# Amp_op3.net
KiCad netlist of a schematic drawn in Altium Designer
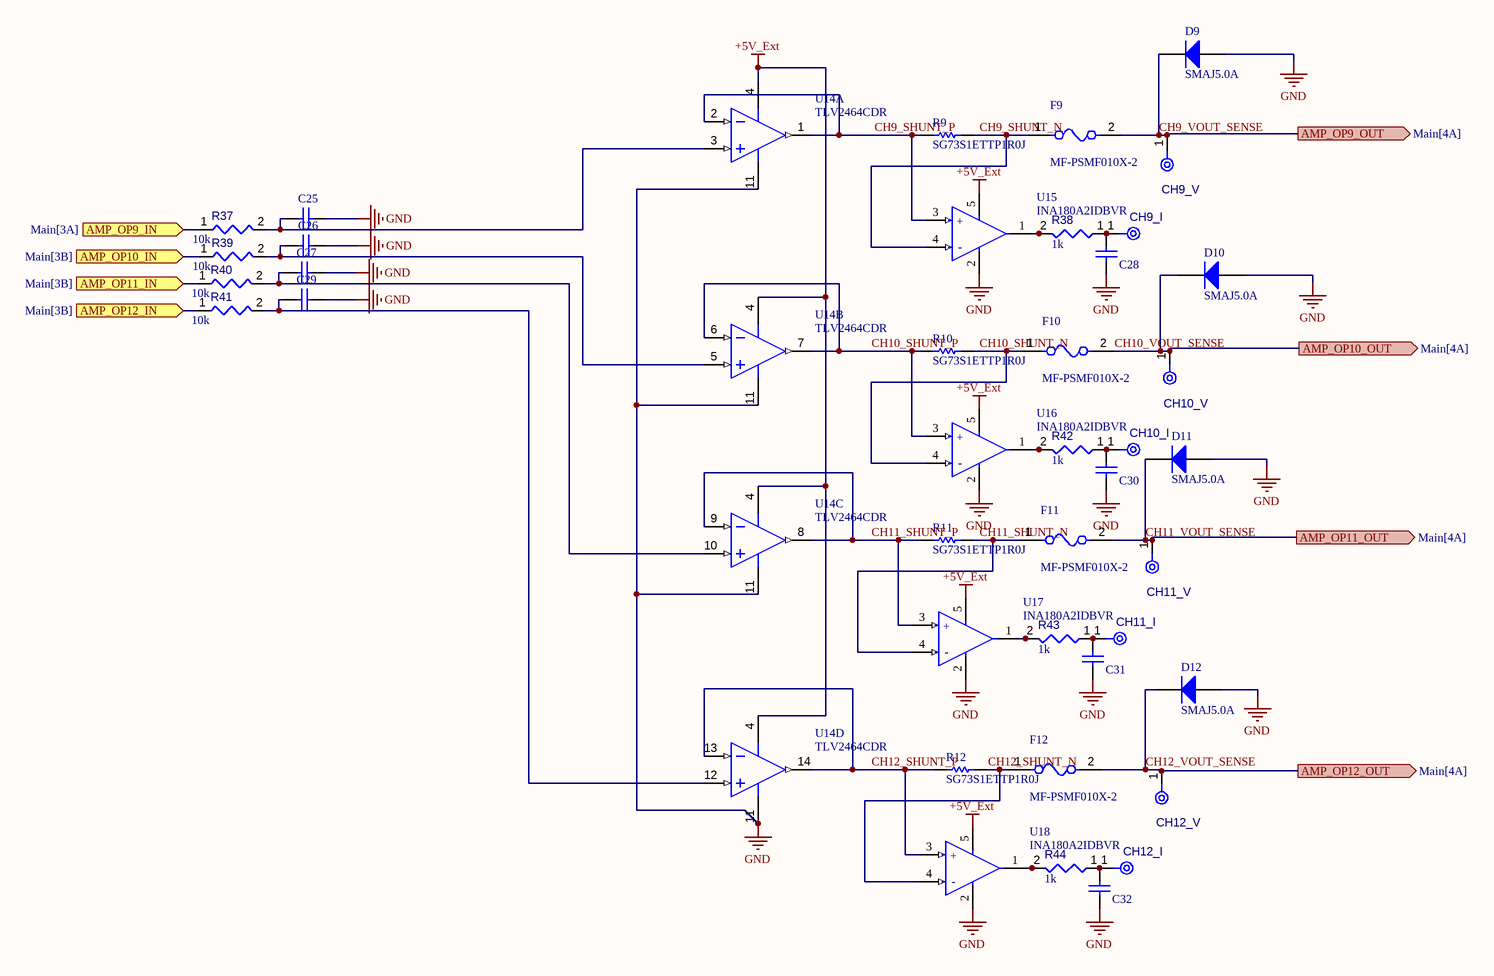
[diagram p0: Amp_op3.SchDoc]

(export (version "E")
  (design (tool "Eeschema 10.0.6"))
  (components
    (comp (ref "C25")
      (value "VJ0603Y104MXJCW1BC")
      (footprint "CAPC1608X95X40NL15T15")
      (fields (field (name "MANUFACTURER") "Vitramon"))
      (libsource (lib "Altium Content Vault") (part "CAP"))
    )
    (comp (ref "C26")
      (value "VJ0603Y104MXJCW1BC")
      (footprint "CAPC1608X95X40NL15T15")
      (fields (field (name "MANUFACTURER") "Vitramon"))
      (libsource (lib "Altium Content Vault") (part "CAP"))
    )
    (comp (ref "C27")
      (value "VJ0603Y104MXJCW1BC")
      (footprint "CAPC1608X95X40NL15T15")
      (fields (field (name "MANUFACTURER") "Vitramon"))
      (libsource (lib "Altium Content Vault") (part "CAP"))
    )
    (comp (ref "C28")
      (value "VJ0603Y104MXJCW1BC")
      (footprint "CAPC1608X95X40NL15T15")
      (fields (field (name "MANUFACTURER") "Vitramon"))
      (libsource (lib "Altium Content Vault") (part "CAP"))
    )
    (comp (ref "C29")
      (value "VJ0603Y104MXJCW1BC")
      (footprint "CAPC1608X95X40NL15T15")
      (fields (field (name "MANUFACTURER") "Vitramon"))
      (libsource (lib "Altium Content Vault") (part "CAP"))
    )
    (comp (ref "C30")
      (value "VJ0603Y104MXJCW1BC")
      (footprint "CAPC1608X95X40NL15T15")
      (fields (field (name "MANUFACTURER") "Vitramon"))
      (libsource (lib "Altium Content Vault") (part "CAP"))
    )
    (comp (ref "C31")
      (value "VJ0603Y104MXJCW1BC")
      (footprint "CAPC1608X95X40NL15T15")
      (fields (field (name "MANUFACTURER") "Vitramon"))
      (libsource (lib "Altium Content Vault") (part "CAP"))
    )
    (comp (ref "C32")
      (value "VJ0603Y104MXJCW1BC")
      (footprint "CAPC1608X95X40NL15T15")
      (fields (field (name "MANUFACTURER") "Vitramon"))
      (libsource (lib "Altium Content Vault") (part "CAP"))
    )
    (comp (ref "CH9_I")
      (value "TPAD6R")
      (footprint "TP06R")
      (description "0.6mm round")
      (libsource (lib "PCEIOT") (part "CMP-00028-00002-2"))
    )
    (comp (ref "CH9_V")
      (value "TPAD6R")
      (footprint "TP06R")
      (description "0.6mm round")
      (libsource (lib "PCEIOT") (part "CMP-00028-00002-2"))
    )
    (comp (ref "CH10_I")
      (value "TPAD6R")
      (footprint "TP06R")
      (description "0.6mm round")
      (libsource (lib "PCEIOT") (part "CMP-00028-00002-2"))
    )
    (comp (ref "CH10_V")
      (value "TPAD6R")
      (footprint "TP06R")
      (description "0.6mm round")
      (libsource (lib "PCEIOT") (part "CMP-00028-00002-2"))
    )
    (comp (ref "CH11_I")
      (value "TPAD6R")
      (footprint "TP06R")
      (description "0.6mm round")
      (libsource (lib "PCEIOT") (part "CMP-00028-00002-2"))
    )
    (comp (ref "CH11_V")
      (value "TPAD6R")
      (footprint "TP06R")
      (description "0.6mm round")
      (libsource (lib "PCEIOT") (part "CMP-00028-00002-2"))
    )
    (comp (ref "CH12_I")
      (value "TPAD6R")
      (footprint "TP06R")
      (description "0.6mm round")
      (libsource (lib "PCEIOT") (part "CMP-00028-00002-2"))
    )
    (comp (ref "CH12_V")
      (value "TPAD6R")
      (footprint "TP06R")
      (description "0.6mm round")
      (libsource (lib "PCEIOT") (part "CMP-00028-00002-2"))
    )
    (comp (ref "D9")
      (value "SMAJ5.0A")
      (footprint "BOUR-SMA-2_V")
      (fields (field (name "MANUFACTURER") "Bourns"))
      (libsource (lib "Altium Content Vault") (part "D-AK-2"))
    )
    (comp (ref "D10")
      (value "SMAJ5.0A")
      (footprint "BOUR-SMA-2_V")
      (fields (field (name "MANUFACTURER") "Bourns"))
      (libsource (lib "Altium Content Vault") (part "D-AK-2"))
    )
    (comp (ref "D11")
      (value "SMAJ5.0A")
      (footprint "BOUR-SMA-2_V")
      (fields (field (name "MANUFACTURER") "Bourns"))
      (libsource (lib "Altium Content Vault") (part "D-AK-2"))
    )
    (comp (ref "D12")
      (value "SMAJ5.0A")
      (footprint "BOUR-SMA-2_V")
      (fields (field (name "MANUFACTURER") "Bourns"))
      (libsource (lib "Altium Content Vault") (part "D-AK-2"))
    )
    (comp (ref "F9")
      (value "MF-PSMF010X-2")
      (footprint "FP-MF-PSMF-MFG")
      (description "PTC RESET FUSE 15V 100MA 0805")
      (fields
        (field (name "OCTOPART") "https://octopart.com/mf-psmf010x-2-bourns-7483441")
        (field (name "MANUFACTURER") "Bourns Inc.")
      )
      (libsource (lib "Altium Content Vault") (part "5bcf9b9f640e542cf0359d10258e979"))
    )
    (comp (ref "F10")
      (value "MF-PSMF010X-2")
      (footprint "FP-MF-PSMF-MFG")
      (description "PTC RESET FUSE 15V 100MA 0805")
      (fields
        (field (name "OCTOPART") "https://octopart.com/mf-psmf010x-2-bourns-7483441")
        (field (name "MANUFACTURER") "Bourns Inc.")
      )
      (libsource (lib "Altium Content Vault") (part "5bcf9b9f640e542cf0359d10258e979"))
    )
    (comp (ref "F11")
      (value "MF-PSMF010X-2")
      (footprint "FP-MF-PSMF-MFG")
      (description "PTC RESET FUSE 15V 100MA 0805")
      (fields
        (field (name "OCTOPART") "https://octopart.com/mf-psmf010x-2-bourns-7483441")
        (field (name "MANUFACTURER") "Bourns Inc.")
      )
      (libsource (lib "Altium Content Vault") (part "5bcf9b9f640e542cf0359d10258e979"))
    )
    (comp (ref "F12")
      (value "MF-PSMF010X-2")
      (footprint "FP-MF-PSMF-MFG")
      (description "PTC RESET FUSE 15V 100MA 0805")
      (fields
        (field (name "OCTOPART") "https://octopart.com/mf-psmf010x-2-bourns-7483441")
        (field (name "MANUFACTURER") "Bourns Inc.")
      )
      (libsource (lib "Altium Content Vault") (part "5bcf9b9f640e542cf0359d10258e979"))
    )
    (comp (ref "R9")
      (value "SG73S1ETTP1R0J")
      (footprint "RESC1005X40X25LL10T10")
      (fields (field (name "MANUFACTURER") "KOA Speer"))
      (libsource (lib "Altium Content Vault") (part "RES"))
    )
    (comp (ref "R10")
      (value "SG73S1ETTP1R0J")
      (footprint "RESC1005X40X25LL10T10")
      (fields (field (name "MANUFACTURER") "KOA Speer"))
      (libsource (lib "Altium Content Vault") (part "RES"))
    )
    (comp (ref "R11")
      (value "SG73S1ETTP1R0J")
      (footprint "RESC1005X40X25LL10T10")
      (fields (field (name "MANUFACTURER") "KOA Speer"))
      (libsource (lib "Altium Content Vault") (part "RES"))
    )
    (comp (ref "R12")
      (value "SG73S1ETTP1R0J")
      (footprint "RESC1005X40X25LL10T10")
      (fields (field (name "MANUFACTURER") "KOA Speer"))
      (libsource (lib "Altium Content Vault") (part "RES"))
    )
    (comp (ref "R37")
      (value "10k")
      (footprint "RESC0603(1608)_L")
      (description "Chip Resistor, 10 KOhm, +/- 1%, 01 W, -55 to 155 degC, 0603 (1608 Metric)")
      (fields (field (name "POWER") "100mW") (field (name "TOLERANCE") "1%"))
      (libsource (lib "PCEIOT") (part "CMP-009-00017-7"))
    )
    (comp (ref "R38")
      (value "1k")
      (footprint "RESC0603(1608)_L")
      (description "Chip Resistor, 1 KOhm, +/-1%, 0.1 W, -55 to 155 degC, 0603 (1608 Metric)")
      (fields (field (name "POWER") "100mW") (field (name "TOLERANCE") "1%"))
      (libsource (lib "PCEIOT") (part "CMP-009-00014-6"))
    )
    (comp (ref "R39")
      (value "10k")
      (footprint "RESC0603(1608)_L")
      (description "Chip Resistor, 10 KOhm, +/- 1%, 01 W, -55 to 155 degC, 0603 (1608 Metric)")
      (fields (field (name "POWER") "100mW") (field (name "TOLERANCE") "1%"))
      (libsource (lib "PCEIOT") (part "CMP-009-00017-7"))
    )
    (comp (ref "R40")
      (value "10k")
      (footprint "RESC0603(1608)_L")
      (description "Chip Resistor, 10 KOhm, +/- 1%, 01 W, -55 to 155 degC, 0603 (1608 Metric)")
      (fields (field (name "POWER") "100mW") (field (name "TOLERANCE") "1%"))
      (libsource (lib "PCEIOT") (part "CMP-009-00017-7"))
    )
    (comp (ref "R41")
      (value "10k")
      (footprint "RESC0603(1608)_L")
      (description "Chip Resistor, 10 KOhm, +/- 1%, 01 W, -55 to 155 degC, 0603 (1608 Metric)")
      (fields (field (name "POWER") "100mW") (field (name "TOLERANCE") "1%"))
      (libsource (lib "PCEIOT") (part "CMP-009-00017-7"))
    )
    (comp (ref "R42")
      (value "1k")
      (footprint "RESC0603(1608)_L")
      (description "Chip Resistor, 1 KOhm, +/-1%, 0.1 W, -55 to 155 degC, 0603 (1608 Metric)")
      (fields (field (name "POWER") "100mW") (field (name "TOLERANCE") "1%"))
      (libsource (lib "PCEIOT") (part "CMP-009-00014-6"))
    )
    (comp (ref "R43")
      (value "1k")
      (footprint "RESC0603(1608)_L")
      (description "Chip Resistor, 1 KOhm, +/-1%, 0.1 W, -55 to 155 degC, 0603 (1608 Metric)")
      (fields (field (name "POWER") "100mW") (field (name "TOLERANCE") "1%"))
      (libsource (lib "PCEIOT") (part "CMP-009-00014-6"))
    )
    (comp (ref "R44")
      (value "1k")
      (footprint "RESC0603(1608)_L")
      (description "Chip Resistor, 1 KOhm, +/-1%, 0.1 W, -55 to 155 degC, 0603 (1608 Metric)")
      (fields (field (name "POWER") "100mW") (field (name "TOLERANCE") "1%"))
      (libsource (lib "PCEIOT") (part "CMP-009-00014-6"))
    )
    (comp (ref "U14")
      (value "TLV2464CDR")
      (footprint "D0014A_N")
      (fields (field (name "MANUFACTURER") "Texas Instruments"))
      (libsource (lib "Altium Content Vault") (part "TI-TLV2464X-XX14"))
    )
    (comp (ref "U15")
      (value "INA180A2IDBVR")
      (footprint "FP-DBV0005A-MFG")
      (description "IC CURR SENSE 1 CIRCUIT SOT23-5")
      (libsource (lib "Altium Content Vault") (part "0a55cf1a948ad01a3239aec1b7efad0"))
    )
    (comp (ref "U16")
      (value "INA180A2IDBVR")
      (footprint "FP-DBV0005A-MFG")
      (description "IC CURR SENSE 1 CIRCUIT SOT23-5")
      (libsource (lib "Altium Content Vault") (part "0a55cf1a948ad01a3239aec1b7efad0"))
    )
    (comp (ref "U17")
      (value "INA180A2IDBVR")
      (footprint "FP-DBV0005A-MFG")
      (description "IC CURR SENSE 1 CIRCUIT SOT23-5")
      (libsource (lib "Altium Content Vault") (part "0a55cf1a948ad01a3239aec1b7efad0"))
    )
    (comp (ref "U18")
      (value "INA180A2IDBVR")
      (footprint "FP-DBV0005A-MFG")
      (description "IC CURR SENSE 1 CIRCUIT SOT23-5")
      (libsource (lib "Altium Content Vault") (part "0a55cf1a948ad01a3239aec1b7efad0"))
    )
  )
  (nets
    (net (code "1") (name "+5V_Ext") (class "Default")
      (node (ref "U14") (pin "4") (pinfunction "VDD+_4") (pintype "power_in"))
      (node (ref "U15") (pin "5") (pinfunction "VS_5") (pintype "power_in"))
      (node (ref "U16") (pin "5") (pinfunction "VS_5") (pintype "power_in"))
      (node (ref "U17") (pin "5") (pinfunction "VS_5") (pintype "power_in"))
      (node (ref "U18") (pin "5") (pinfunction "VS_5") (pintype "power_in"))
    )
    (net (code "2") (name "/AMP_OP9_IN") (class "Default")
      (node (ref "R37") (pin "1") (pinfunction "1_1") (pintype "passive"))
    )
    (net (code "3") (name "/AMP_OP10_IN") (class "Default")
      (node (ref "R39") (pin "1") (pinfunction "1_1") (pintype "passive"))
    )
    (net (code "4") (name "/AMP_OP11_IN") (class "Default")
      (node (ref "R40") (pin "1") (pinfunction "1_1") (pintype "passive"))
    )
    (net (code "5") (name "/AMP_OP12_IN") (class "Default")
      (node (ref "R41") (pin "1") (pinfunction "1_1") (pintype "passive"))
    )
    (net (code "6") (name "/CH9_SHUNT_N") (class "Default")
      (node (ref "F9") (pin "1") (pinfunction "1_1") (pintype "passive"))
      (node (ref "R9") (pin "2") (pinfunction "2_2") (pintype "passive"))
      (node (ref "U15") (pin "4") (pinfunction "IN-_4") (pintype "input"))
    )
    (net (code "7") (name "/CH9_SHUNT_P") (class "Default")
      (node (ref "R9") (pin "1") (pinfunction "1_1") (pintype "passive"))
      (node (ref "U14") (pin "1") (pinfunction "OUT1_1") (pintype "output"))
      (node (ref "U14") (pin "2") (pinfunction "IN1-_2") (pintype "input"))
      (node (ref "U15") (pin "3") (pinfunction "IN+_3") (pintype "input"))
    )
    (net (code "8") (name "/CH9_VOUT_SENSE") (class "Default")
      (node (ref "CH9_V") (pin "1") (pinfunction "TP_1") (pintype "passive"))
      (node (ref "D9") (pin "2") (pinfunction "K_2") (pintype "passive"))
      (node (ref "F9") (pin "2") (pinfunction "2_2") (pintype "passive"))
    )
    (net (code "9") (name "/CH10_SHUNT_N") (class "Default")
      (node (ref "F10") (pin "1") (pinfunction "1_1") (pintype "passive"))
      (node (ref "R10") (pin "2") (pinfunction "2_2") (pintype "passive"))
      (node (ref "U16") (pin "4") (pinfunction "IN-_4") (pintype "input"))
    )
    (net (code "10") (name "/CH10_SHUNT_P") (class "Default")
      (node (ref "R10") (pin "1") (pinfunction "1_1") (pintype "passive"))
      (node (ref "U14") (pin "6") (pinfunction "IN2-_6") (pintype "input"))
      (node (ref "U14") (pin "7") (pinfunction "OUT2_7") (pintype "output"))
      (node (ref "U16") (pin "3") (pinfunction "IN+_3") (pintype "input"))
    )
    (net (code "11") (name "/CH10_VOUT_SENSE") (class "Default")
      (node (ref "CH10_V") (pin "1") (pinfunction "TP_1") (pintype "passive"))
      (node (ref "D10") (pin "2") (pinfunction "K_2") (pintype "passive"))
      (node (ref "F10") (pin "2") (pinfunction "2_2") (pintype "passive"))
    )
    (net (code "12") (name "/CH11_SHUNT_N") (class "Default")
      (node (ref "F11") (pin "1") (pinfunction "1_1") (pintype "passive"))
      (node (ref "R11") (pin "2") (pinfunction "2_2") (pintype "passive"))
      (node (ref "U17") (pin "4") (pinfunction "IN-_4") (pintype "input"))
    )
    (net (code "13") (name "/CH11_SHUNT_P") (class "Default")
      (node (ref "R11") (pin "1") (pinfunction "1_1") (pintype "passive"))
      (node (ref "U14") (pin "8") (pinfunction "OUT3_8") (pintype "output"))
      (node (ref "U14") (pin "9") (pinfunction "IN3-_9") (pintype "input"))
      (node (ref "U17") (pin "3") (pinfunction "IN+_3") (pintype "input"))
    )
    (net (code "14") (name "/CH11_VOUT_SENSE") (class "Default")
      (node (ref "CH11_V") (pin "1") (pinfunction "TP_1") (pintype "passive"))
      (node (ref "D11") (pin "2") (pinfunction "K_2") (pintype "passive"))
      (node (ref "F11") (pin "2") (pinfunction "2_2") (pintype "passive"))
    )
    (net (code "15") (name "/CH12_SHUNT_N") (class "Default")
      (node (ref "F12") (pin "1") (pinfunction "1_1") (pintype "passive"))
      (node (ref "R12") (pin "2") (pinfunction "2_2") (pintype "passive"))
      (node (ref "U18") (pin "4") (pinfunction "IN-_4") (pintype "input"))
    )
    (net (code "16") (name "/CH12_SHUNT_P") (class "Default")
      (node (ref "R12") (pin "1") (pinfunction "1_1") (pintype "passive"))
      (node (ref "U14") (pin "13") (pinfunction "IN4-_13") (pintype "input"))
      (node (ref "U14") (pin "14") (pinfunction "OUT4_14") (pintype "output"))
      (node (ref "U18") (pin "3") (pinfunction "IN+_3") (pintype "input"))
    )
    (net (code "17") (name "/CH12_VOUT_SENSE") (class "Default")
      (node (ref "CH12_V") (pin "1") (pinfunction "TP_1") (pintype "passive"))
      (node (ref "D12") (pin "2") (pinfunction "K_2") (pintype "passive"))
      (node (ref "F12") (pin "2") (pinfunction "2_2") (pintype "passive"))
    )
    (net (code "18") (name "GND") (class "Default")
      (node (ref "C25") (pin "2") (pinfunction "2_2") (pintype "passive"))
      (node (ref "C26") (pin "2") (pinfunction "2_2") (pintype "passive"))
      (node (ref "C27") (pin "2") (pinfunction "2_2") (pintype "passive"))
      (node (ref "C28") (pin "2") (pinfunction "2_2") (pintype "passive"))
      (node (ref "C29") (pin "2") (pinfunction "2_2") (pintype "passive"))
      (node (ref "C30") (pin "2") (pinfunction "2_2") (pintype "passive"))
      (node (ref "C31") (pin "2") (pinfunction "2_2") (pintype "passive"))
      (node (ref "C32") (pin "2") (pinfunction "2_2") (pintype "passive"))
      (node (ref "D10") (pin "1") (pinfunction "A_1") (pintype "passive"))
      (node (ref "D11") (pin "1") (pinfunction "A_1") (pintype "passive"))
      (node (ref "D12") (pin "1") (pinfunction "A_1") (pintype "passive"))
      (node (ref "D9") (pin "1") (pinfunction "A_1") (pintype "passive"))
      (node (ref "U14") (pin "11") (pinfunction "GND_11") (pintype "power_in"))
      (node (ref "U15") (pin "2") (pinfunction "GND_2") (pintype "power_in"))
      (node (ref "U16") (pin "2") (pinfunction "GND_2") (pintype "power_in"))
      (node (ref "U17") (pin "2") (pinfunction "GND_2") (pintype "power_in"))
      (node (ref "U18") (pin "2") (pinfunction "GND_2") (pintype "power_in"))
    )
    (net (code "19") (name "Net-(CH9_I-TP)") (class "Default")
      (node (ref "C28") (pin "1") (pinfunction "1_1") (pintype "passive"))
      (node (ref "CH9_I") (pin "1") (pinfunction "TP_1") (pintype "passive"))
      (node (ref "R38") (pin "1") (pinfunction "1_1") (pintype "passive"))
    )
    (net (code "20") (name "Net-(CH10_I-TP)") (class "Default")
      (node (ref "C30") (pin "1") (pinfunction "1_1") (pintype "passive"))
      (node (ref "CH10_I") (pin "1") (pinfunction "TP_1") (pintype "passive"))
      (node (ref "R42") (pin "1") (pinfunction "1_1") (pintype "passive"))
    )
    (net (code "21") (name "Net-(CH11_I-TP)") (class "Default")
      (node (ref "C31") (pin "1") (pinfunction "1_1") (pintype "passive"))
      (node (ref "CH11_I") (pin "1") (pinfunction "TP_1") (pintype "passive"))
      (node (ref "R43") (pin "1") (pinfunction "1_1") (pintype "passive"))
    )
    (net (code "22") (name "Net-(CH12_I-TP)") (class "Default")
      (node (ref "C32") (pin "1") (pinfunction "1_1") (pintype "passive"))
      (node (ref "CH12_I") (pin "1") (pinfunction "TP_1") (pintype "passive"))
      (node (ref "R44") (pin "1") (pinfunction "1_1") (pintype "passive"))
    )
    (net (code "23") (name "Net-(U14A-IN1+)") (class "Default")
      (node (ref "C25") (pin "1") (pinfunction "1_1") (pintype "passive"))
      (node (ref "R37") (pin "2") (pinfunction "2_2") (pintype "passive"))
      (node (ref "U14") (pin "3") (pinfunction "IN1+_3") (pintype "input"))
    )
    (net (code "24") (name "Net-(U14B-IN2+)") (class "Default")
      (node (ref "C26") (pin "1") (pinfunction "1_1") (pintype "passive"))
      (node (ref "R39") (pin "2") (pinfunction "2_2") (pintype "passive"))
      (node (ref "U14") (pin "5") (pinfunction "IN2+_5") (pintype "input"))
    )
    (net (code "25") (name "Net-(U14C-IN3+)") (class "Default")
      (node (ref "C27") (pin "1") (pinfunction "1_1") (pintype "passive"))
      (node (ref "R40") (pin "2") (pinfunction "2_2") (pintype "passive"))
      (node (ref "U14") (pin "10") (pinfunction "IN3+_10") (pintype "input"))
    )
    (net (code "26") (name "Net-(U14D-IN4+)") (class "Default")
      (node (ref "C29") (pin "1") (pinfunction "1_1") (pintype "passive"))
      (node (ref "R41") (pin "2") (pinfunction "2_2") (pintype "passive"))
      (node (ref "U14") (pin "12") (pinfunction "IN4+_12") (pintype "input"))
    )
    (net (code "27") (name "Net-(U15-OUT)") (class "Default")
      (node (ref "R38") (pin "2") (pinfunction "2_2") (pintype "passive"))
      (node (ref "U15") (pin "1") (pinfunction "OUT_1") (pintype "passive"))
    )
    (net (code "28") (name "Net-(U16-OUT)") (class "Default")
      (node (ref "R42") (pin "2") (pinfunction "2_2") (pintype "passive"))
      (node (ref "U16") (pin "1") (pinfunction "OUT_1") (pintype "passive"))
    )
    (net (code "29") (name "Net-(U17-OUT)") (class "Default")
      (node (ref "R43") (pin "2") (pinfunction "2_2") (pintype "passive"))
      (node (ref "U17") (pin "1") (pinfunction "OUT_1") (pintype "passive"))
    )
    (net (code "30") (name "Net-(U18-OUT)") (class "Default")
      (node (ref "R44") (pin "2") (pinfunction "2_2") (pintype "passive"))
      (node (ref "U18") (pin "1") (pinfunction "OUT_1") (pintype "passive"))
    )
  )
)
